# USB-C_Host_Shield.net
KiCad netlist of a schematic drawn in EAGLE
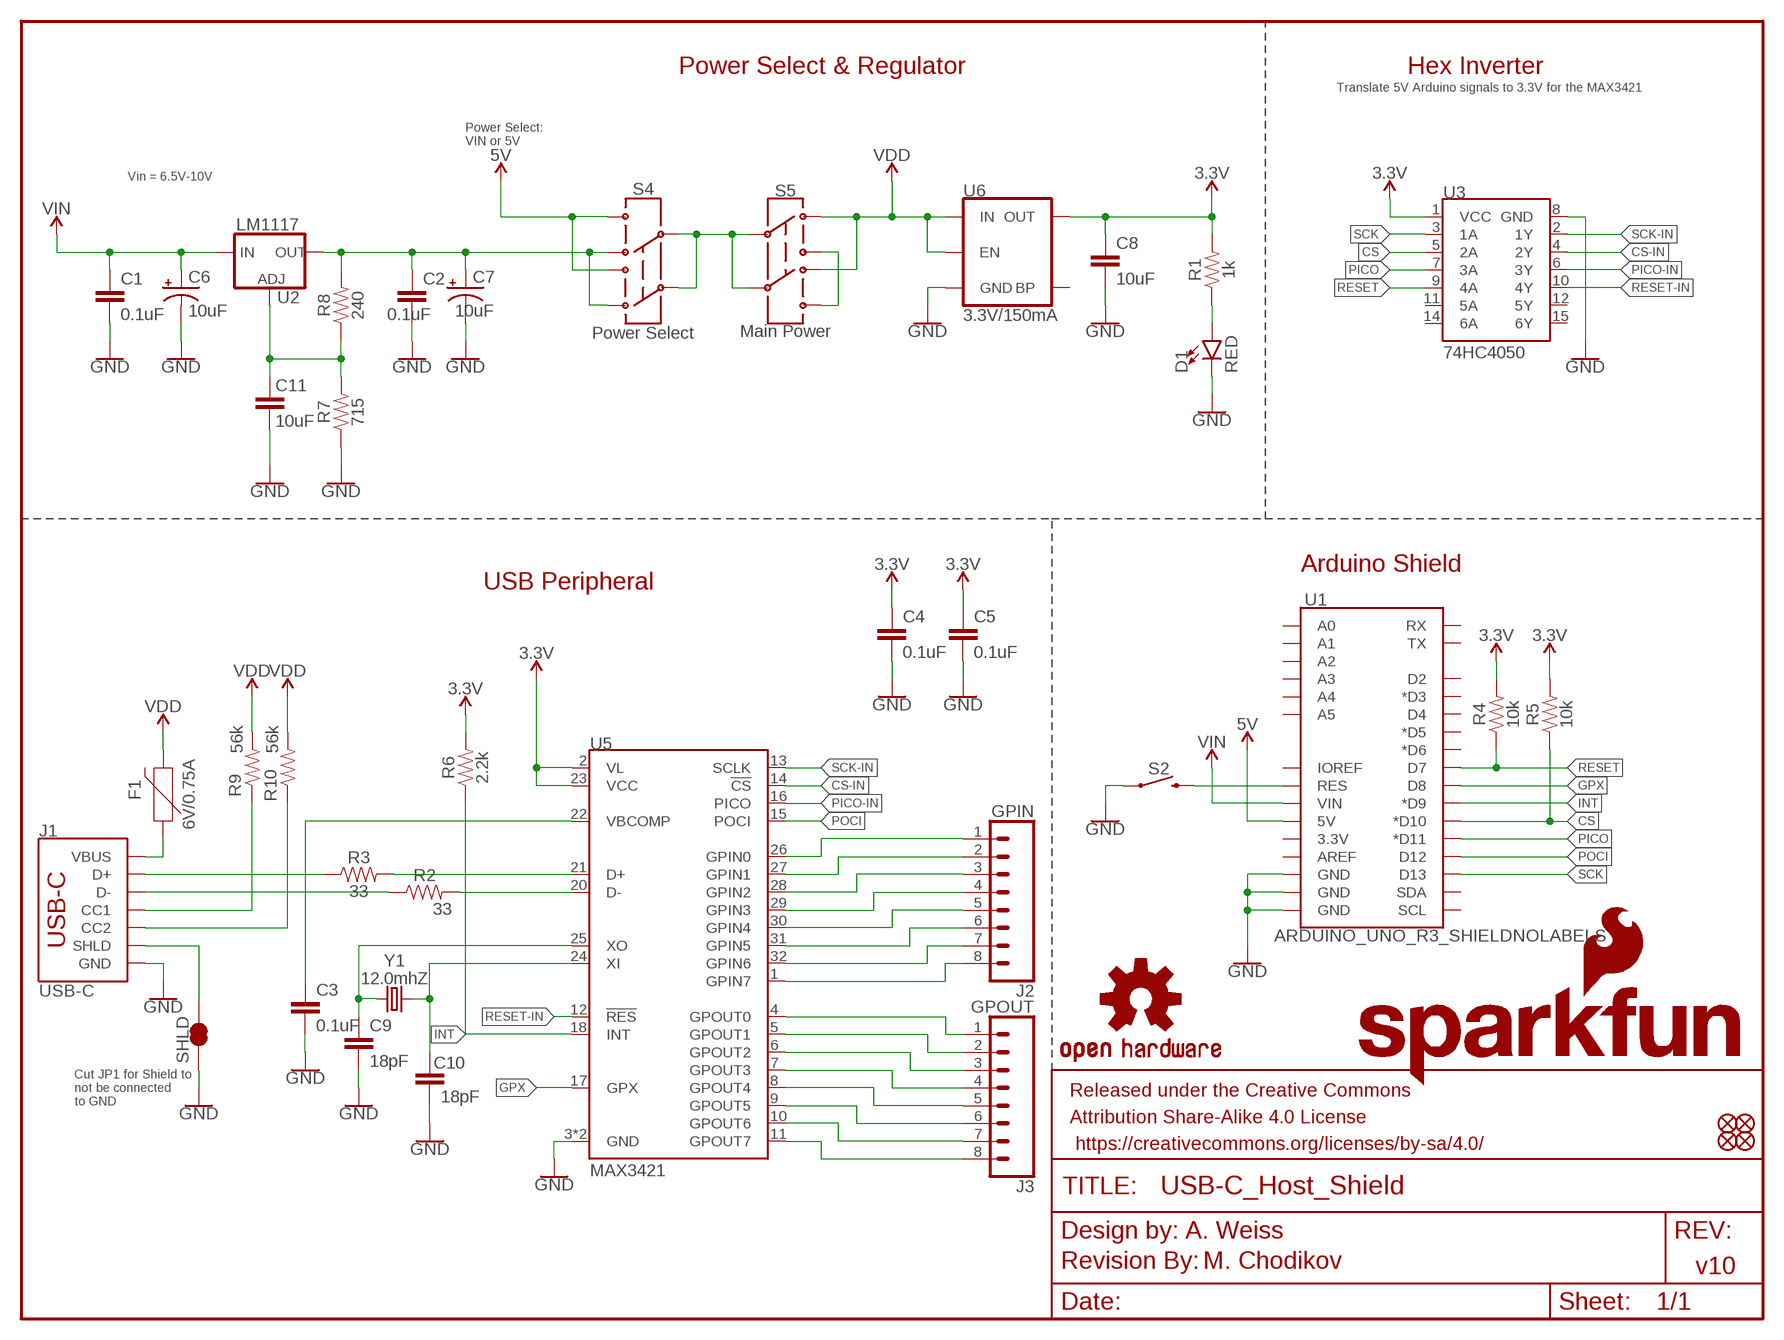
[diagram p0: schematic, sheet 1]

(export (version "E")
  (design (tool "Eeschema 10.0.6"))
  (components
    (comp (ref "C1")
      (value "0.1uF")
      (footprint "eagle-import:0603")
      (libsource (lib "eagle-import") (part "0.1UF-0603-25V-(+80/-20%)"))
    )
    (comp (ref "C2")
      (value "0.1uF")
      (footprint "eagle-import:0603")
      (libsource (lib "eagle-import") (part "0.1UF-0603-25V-(+80/-20%)"))
    )
    (comp (ref "C3")
      (value "0.1uF")
      (footprint "eagle-import:0603")
      (libsource (lib "eagle-import") (part "0.1UF-0603-25V-(+80/-20%)"))
    )
    (comp (ref "C4")
      (value "0.1uF")
      (footprint "eagle-import:0603")
      (libsource (lib "eagle-import") (part "0.1UF-0603-25V-(+80/-20%)"))
    )
    (comp (ref "C5")
      (value "0.1uF")
      (footprint "eagle-import:0603")
      (libsource (lib "eagle-import") (part "0.1UF-0603-25V-(+80/-20%)"))
    )
    (comp (ref "C6")
      (value "10uF")
      (footprint "eagle-import:EIA3216")
      (libsource (lib "eagle-import") (part "10UF-POLAR-EIA3216-16V-10%(TANT)"))
    )
    (comp (ref "C7")
      (value "10uF")
      (footprint "eagle-import:EIA3216")
      (libsource (lib "eagle-import") (part "10UF-POLAR-EIA3216-16V-10%(TANT)"))
    )
    (comp (ref "C8")
      (value "10uF")
      (footprint "eagle-import:0603")
      (libsource (lib "eagle-import") (part "10UF-0603-6.3V-20%"))
    )
    (comp (ref "C9")
      (value "18pF")
      (footprint "eagle-import:0603")
      (libsource (lib "eagle-import") (part "18PF-0603-50V-5%"))
    )
    (comp (ref "C10")
      (value "18pF")
      (footprint "eagle-import:0603")
      (libsource (lib "eagle-import") (part "18PF-0603-50V-5%"))
    )
    (comp (ref "C11")
      (value "10uF")
      (footprint "eagle-import:0805")
      (libsource (lib "eagle-import") (part "10UF-0805-25V-10%"))
    )
    (comp (ref "D1")
      (value "RED")
      (footprint "eagle-import:LED-0603")
      (libsource (lib "eagle-import") (part "LED-RED0603"))
    )
    (comp (ref "F1")
      (value "6V/0.75A")
      (footprint "eagle-import:1206")
      (libsource (lib "eagle-import") (part "PPTC_0.75A"))
    )
    (comp (ref "FD1")
      (value "FIDUCIALUFIDUCIAL")
      (footprint "eagle-import:FIDUCIAL-MICRO")
      (libsource (lib "eagle-import") (part "FIDUCIALUFIDUCIAL"))
    )
    (comp (ref "FD2")
      (value "FIDUCIALUFIDUCIAL")
      (footprint "eagle-import:FIDUCIAL-MICRO")
      (libsource (lib "eagle-import") (part "FIDUCIALUFIDUCIAL"))
    )
    (comp (ref "FD3")
      (value "FIDUCIALUFIDUCIAL")
      (footprint "eagle-import:FIDUCIAL-MICRO")
      (libsource (lib "eagle-import") (part "FIDUCIALUFIDUCIAL"))
    )
    (comp (ref "FD4")
      (value "FIDUCIALUFIDUCIAL")
      (footprint "eagle-import:FIDUCIAL-MICRO")
      (libsource (lib "eagle-import") (part "FIDUCIALUFIDUCIAL"))
    )
    (comp (ref "FRAME1")
      (value "FRAME-LETTER")
      (footprint "eagle-import:CREATIVE_COMMONS")
      (libsource (lib "eagle-import") (part "FRAME-LETTER"))
    )
    (comp (ref "J1")
      (value "USB-C")
      (footprint "eagle-import:USB-C-16P-2LAYER-PADS")
      (libsource (lib "eagle-import") (part "USB_C_2-LAYER_PADS"))
    )
    (comp (ref "J2")
      (value "GPIN")
      (footprint "eagle-import:1X08")
      (libsource (lib "eagle-import") (part "CONN_08{dblquote}"))
    )
    (comp (ref "J3")
      (value "GPOUT")
      (footprint "eagle-import:1X08")
      (libsource (lib "eagle-import") (part "CONN_08{dblquote}"))
    )
    (comp (ref "LOGO1")
      (value "OSHW-LOGOM")
      (footprint "eagle-import:OSHW-LOGO-M")
      (libsource (lib "eagle-import") (part "OSHW-LOGOM"))
    )
    (comp (ref "LOGO2")
      (value "SFE_LOGO_NAME_FLAME.1_INCH")
      (footprint "eagle-import:SFE_LOGO_NAME_FLAME_.1")
      (libsource (lib "eagle-import") (part "SFE_LOGO_NAME_FLAME.1_INCH"))
    )
    (comp (ref "LOGO3")
      (value "SFE_LOGO_NAME_FLAME.2_INCH")
      (footprint "eagle-import:SFE_LOGO_NAME_FLAME_.2")
      (libsource (lib "eagle-import") (part "SFE_LOGO_NAME_FLAME.2_INCH"))
    )
    (comp (ref "LOGO7")
      (value "REVISION")
      (footprint "eagle-import:REVISION")
      (libsource (lib "eagle-import") (part "REVISION"))
    )
    (comp (ref "R1")
      (value "1k")
      (footprint "eagle-import:0603")
      (libsource (lib "eagle-import") (part "1KOHM-0603-1/10W-1%"))
    )
    (comp (ref "R2")
      (value "33")
      (footprint "eagle-import:0603")
      (libsource (lib "eagle-import") (part "33OHM-0603-1/10W-1%"))
    )
    (comp (ref "R3")
      (value "33")
      (footprint "eagle-import:0603")
      (libsource (lib "eagle-import") (part "33OHM-0603-1/10W-1%"))
    )
    (comp (ref "R4")
      (value "10k")
      (footprint "eagle-import:0603")
      (libsource (lib "eagle-import") (part "10KOHM-0603-1/10W-1%"))
    )
    (comp (ref "R5")
      (value "10k")
      (footprint "eagle-import:0603")
      (libsource (lib "eagle-import") (part "10KOHM-0603-1/10W-1%"))
    )
    (comp (ref "R6")
      (value "2.2k")
      (footprint "eagle-import:0603")
      (libsource (lib "eagle-import") (part "2.2KOHM-0603-1/10W-1%"))
    )
    (comp (ref "R7")
      (value "715")
      (footprint "eagle-import:0603")
      (libsource (lib "eagle-import") (part "715OHM-0603-1/10W-1%"))
    )
    (comp (ref "R8")
      (value "240")
      (footprint "eagle-import:0603")
      (libsource (lib "eagle-import") (part "240OHM-0603-1/10W-1%"))
    )
    (comp (ref "R9")
      (value "56k")
      (footprint "eagle-import:0603")
      (libsource (lib "eagle-import") (part "56KOHM"))
    )
    (comp (ref "R10")
      (value "56k")
      (footprint "eagle-import:0603")
      (libsource (lib "eagle-import") (part "56KOHM"))
    )
    (comp (ref "S2")
      (value "MOMENTARY-SWITCH-SPST-SMD-5.2MM-TALL")
      (footprint "eagle-import:TACTILE_SWITCH_SMD_5.2MM")
      (libsource (lib "eagle-import") (part "MOMENTARY-SWITCH-SPST-SMD-5.2MM-TALL"))
    )
    (comp (ref "S4")
      (value "Power Select")
      (footprint "eagle-import:SWITCH_DPDT_SMD_AYZ0202")
      (libsource (lib "eagle-import") (part "SWITCH-DPDT-SMD-AYZ0202"))
    )
    (comp (ref "S5")
      (value "Main Power")
      (footprint "eagle-import:SWITCH_DPDT_SMD_AYZ0202")
      (libsource (lib "eagle-import") (part "SWITCH-DPDT-SMD-AYZ0202"))
    )
    (comp (ref "SHLD")
      (value "JUMPER-SMT_2_NC_TRACE_SILK")
      (footprint "eagle-import:SMT-JUMPER_2_NC_TRACE_SILK")
      (libsource (lib "eagle-import") (part "JUMPER-SMT_2_NC_TRACE_SILK"))
    )
    (comp (ref "U1")
      (value "ARDUINO_UNO_R3_SHIELDNOLABELS")
      (footprint "eagle-import:UNO_R3_SHIELD_NOLABELS")
      (libsource (lib "eagle-import") (part "ARDUINO_UNO_R3_SHIELDNOLABELS"))
    )
    (comp (ref "U2")
      (value "LM1117")
      (footprint "eagle-import:SOT223")
      (libsource (lib "eagle-import") (part "V_REG_LM1117SOT223"))
    )
    (comp (ref "U3")
      (value "74HC4050")
      (footprint "eagle-import:SO16")
      (libsource (lib "eagle-import") (part "HEX_CONVERTER"))
    )
    (comp (ref "U5")
      (value "MAX3421")
      (footprint "eagle-import:TQFP32")
      (libsource (lib "eagle-import") (part "MAX3421"))
    )
    (comp (ref "U6")
      (value "3.3V/150mA")
      (footprint "eagle-import:SOT23-5")
      (libsource (lib "eagle-import") (part "V_REG_MIC52053.3V"))
    )
    (comp (ref "Y1")
      (value "12.0mhZ")
      (footprint "eagle-import:CRYSTAL-SMD-2X2.5MM")
      (libsource (lib "eagle-import") (part "CRYSTAL-12MHZ"))
    )
  )
  (nets
    (net (code "1") (name "3.3V") (class "Default")
      (node (ref "C4") (pin "1") (pinfunction "1_1") (pintype "passive"))
      (node (ref "C5") (pin "1") (pinfunction "1_1") (pintype "passive"))
      (node (ref "C8") (pin "1") (pinfunction "1_1") (pintype "passive"))
      (node (ref "R1") (pin "2") (pinfunction "2_2") (pintype "passive"))
      (node (ref "R4") (pin "2") (pinfunction "2_2") (pintype "passive"))
      (node (ref "R5") (pin "2") (pinfunction "2_2") (pintype "passive"))
      (node (ref "R6") (pin "2") (pinfunction "2_2") (pintype "passive"))
      (node (ref "U3") (pin "1") (pinfunction "VCC_1") (pintype "bidirectional"))
      (node (ref "U5") (pin "2") (pinfunction "VL_2") (pintype "input"))
      (node (ref "U5") (pin "23") (pinfunction "VCC_23") (pintype "input"))
      (node (ref "U6") (pin "5") (pinfunction "OUT_5") (pintype "passive"))
    )
    (net (code "2") (name "5V") (class "Default")
      (node (ref "S4") (pin "1") (pinfunction "1_1") (pintype "bidirectional"))
      (node (ref "S4") (pin "4") (pinfunction "4_4") (pintype "bidirectional"))
      (node (ref "U1") (pin "5V") (pinfunction "5V_5V") (pintype "bidirectional"))
    )
    (net (code "3") (name "CS") (class "Default")
      (node (ref "R5") (pin "1") (pinfunction "1_1") (pintype "passive"))
      (node (ref "U1") (pin "D10") (pinfunction "*D10_D10") (pintype "bidirectional"))
      (node (ref "U3") (pin "5") (pinfunction "2A_5") (pintype "bidirectional"))
    )
    (net (code "4") (name "CS-IN") (class "Default")
      (node (ref "U3") (pin "4") (pinfunction "2Y_4") (pintype "bidirectional"))
      (node (ref "U5") (pin "14") (pinfunction "~{CS}_14") (pintype "input"))
    )
    (net (code "5") (name "GND") (class "Default")
      (node (ref "C1") (pin "2") (pinfunction "2_2") (pintype "passive"))
      (node (ref "C10") (pin "2") (pinfunction "2_2") (pintype "passive"))
      (node (ref "C11") (pin "2") (pinfunction "2_2") (pintype "passive"))
      (node (ref "C2") (pin "2") (pinfunction "2_2") (pintype "passive"))
      (node (ref "C3") (pin "2") (pinfunction "2_2") (pintype "passive"))
      (node (ref "C4") (pin "2") (pinfunction "2_2") (pintype "passive"))
      (node (ref "C5") (pin "2") (pinfunction "2_2") (pintype "passive"))
      (node (ref "C6") (pin "-") (pinfunction "-_-") (pintype "passive"))
      (node (ref "C7") (pin "-") (pinfunction "-_-") (pintype "passive"))
      (node (ref "C8") (pin "2") (pinfunction "2_2") (pintype "passive"))
      (node (ref "C9") (pin "2") (pinfunction "2_2") (pintype "passive"))
      (node (ref "D1") (pin "C") (pinfunction "C_C") (pintype "passive"))
      (node (ref "J1") (pin "GND") (pinfunction "GND_GND") (pintype "bidirectional"))
      (node (ref "J1") (pin "GND2") (pinfunction "GND_GND2") (pintype "bidirectional"))
      (node (ref "R7") (pin "1") (pinfunction "1_1") (pintype "passive"))
      (node (ref "S2") (pin "1") (pinfunction "1_1") (pintype "passive"))
      (node (ref "SHLD") (pin "1") (pinfunction "1_1") (pintype "passive"))
      (node (ref "U1") (pin "GND@0") (pinfunction "GND_GND@0") (pintype "bidirectional"))
      (node (ref "U1") (pin "GND@1") (pinfunction "GND_GND@1") (pintype "bidirectional"))
      (node (ref "U1") (pin "GND@2") (pinfunction "GND_GND@2") (pintype "bidirectional"))
      (node (ref "U3") (pin "8") (pinfunction "GND_8") (pintype "bidirectional"))
      (node (ref "U5") (pin "19") (pinfunction "GND_19") (pintype "input"))
      (node (ref "U5") (pin "3") (pinfunction "GND_3") (pintype "input"))
      (node (ref "U6") (pin "2") (pinfunction "GND_2") (pintype "input"))
    )
    (net (code "6") (name "GPX") (class "Default")
      (node (ref "U1") (pin "D8") (pinfunction "D8_D8") (pintype "bidirectional"))
      (node (ref "U5") (pin "17") (pinfunction "GPX_17") (pintype "output"))
    )
    (net (code "7") (name "INT") (class "Default")
      (node (ref "R6") (pin "1") (pinfunction "1_1") (pintype "passive"))
      (node (ref "U1") (pin "D9") (pinfunction "*D9_D9") (pintype "bidirectional"))
      (node (ref "U5") (pin "18") (pinfunction "INT_18") (pintype "output"))
    )
    (net (code "8") (name "Net-(C2-Pad1)") (class "Default")
      (node (ref "C2") (pin "1") (pinfunction "1_1") (pintype "passive"))
      (node (ref "C7") (pin "+") (pinfunction "+_+") (pintype "passive"))
      (node (ref "R8") (pin "2") (pinfunction "2_2") (pintype "passive"))
      (node (ref "S4") (pin "3") (pinfunction "3_3") (pintype "bidirectional"))
      (node (ref "S4") (pin "6") (pinfunction "6_6") (pintype "bidirectional"))
      (node (ref "U2") (pin "2") (pinfunction "OUT_2") (pintype "output"))
      (node (ref "U2") (pin "4") (pinfunction "OUT_4") (pintype "output"))
    )
    (net (code "9") (name "Net-(D1-PadA)") (class "Default")
      (node (ref "D1") (pin "A") (pinfunction "A_A") (pintype "passive"))
      (node (ref "R1") (pin "1") (pinfunction "1_1") (pintype "passive"))
    )
    (net (code "10") (name "Net-(F1-Pad1)") (class "Default")
      (node (ref "F1") (pin "1") (pinfunction "1_1") (pintype "bidirectional"))
      (node (ref "J1") (pin "VBUS1") (pinfunction "VBUS_VBUS1") (pintype "bidirectional"))
      (node (ref "J1") (pin "VBUS2") (pinfunction "VBUS_VBUS2") (pintype "bidirectional"))
    )
    (net (code "11") (name "Net-(J1-CC1)") (class "Default")
      (node (ref "J1") (pin "A5") (pinfunction "CC1_A5") (pintype "bidirectional"))
      (node (ref "R9") (pin "1") (pinfunction "1_1") (pintype "passive"))
    )
    (net (code "12") (name "Net-(J1-CC2)") (class "Default")
      (node (ref "J1") (pin "B5") (pinfunction "CC2_B5") (pintype "bidirectional"))
      (node (ref "R10") (pin "1") (pinfunction "1_1") (pintype "passive"))
    )
    (net (code "13") (name "Net-(J1-D+-PadA6)") (class "Default")
      (node (ref "J1") (pin "A6") (pinfunction "D+_A6") (pintype "bidirectional"))
      (node (ref "J1") (pin "B6") (pinfunction "D+_B6") (pintype "bidirectional"))
      (node (ref "R3") (pin "1") (pinfunction "1_1") (pintype "passive"))
    )
    (net (code "14") (name "Net-(J1-D--PadA7)") (class "Default")
      (node (ref "J1") (pin "A7") (pinfunction "D-_A7") (pintype "bidirectional"))
      (node (ref "J1") (pin "B7") (pinfunction "D-_B7") (pintype "bidirectional"))
      (node (ref "R2") (pin "1") (pinfunction "1_1") (pintype "passive"))
    )
    (net (code "15") (name "Net-(J1-SHLD-PadSHLD1)") (class "Default")
      (node (ref "J1") (pin "SHLD1") (pinfunction "SHLD_SHLD1") (pintype "bidirectional"))
      (node (ref "J1") (pin "SHLD2") (pinfunction "SHLD_SHLD2") (pintype "bidirectional"))
      (node (ref "J1") (pin "SHLD3") (pinfunction "SHLD_SHLD3") (pintype "bidirectional"))
      (node (ref "J1") (pin "SHLD4") (pinfunction "SHLD_SHLD4") (pintype "bidirectional"))
      (node (ref "SHLD") (pin "2") (pinfunction "2_2") (pintype "passive"))
    )
    (net (code "16") (name "Net-(S2-2)") (class "Default")
      (node (ref "S2") (pin "3") (pinfunction "2_3") (pintype "passive"))
      (node (ref "U1") (pin "RES") (pinfunction "RES_RES") (pintype "bidirectional"))
    )
    (net (code "17") (name "Net-(S4-Pad2)") (class "Default")
      (node (ref "S4") (pin "2") (pinfunction "2_2") (pintype "bidirectional"))
      (node (ref "S4") (pin "5") (pinfunction "5_5") (pintype "bidirectional"))
      (node (ref "S5") (pin "2") (pinfunction "2_2") (pintype "bidirectional"))
      (node (ref "S5") (pin "5") (pinfunction "5_5") (pintype "bidirectional"))
    )
    (net (code "18") (name "Net-(S5-Pad1)") (class "Default")
      (node (ref "S5") (pin "1") (pinfunction "1_1") (pintype "bidirectional"))
      (node (ref "S5") (pin "4") (pinfunction "4_4") (pintype "bidirectional"))
    )
    (net (code "19") (name "Net-(U2-ADJ)") (class "Default")
      (node (ref "C11") (pin "1") (pinfunction "1_1") (pintype "passive"))
      (node (ref "R7") (pin "2") (pinfunction "2_2") (pintype "passive"))
      (node (ref "R8") (pin "1") (pinfunction "1_1") (pintype "passive"))
      (node (ref "U2") (pin "1") (pinfunction "ADJ_1") (pintype "input"))
    )
    (net (code "20") (name "Net-(U5-D+)") (class "Default")
      (node (ref "R3") (pin "2") (pinfunction "2_2") (pintype "passive"))
      (node (ref "U5") (pin "21") (pinfunction "D+_21") (pintype "bidirectional"))
    )
    (net (code "21") (name "Net-(U5-D-)") (class "Default")
      (node (ref "R2") (pin "2") (pinfunction "2_2") (pintype "passive"))
      (node (ref "U5") (pin "20") (pinfunction "D-_20") (pintype "bidirectional"))
    )
    (net (code "22") (name "Net-(U5-GPIN0)") (class "Default")
      (node (ref "J2") (pin "1") (pinfunction "1_1") (pintype "passive"))
      (node (ref "U5") (pin "26") (pinfunction "GPIN0_26") (pintype "input"))
    )
    (net (code "23") (name "Net-(U5-GPIN1)") (class "Default")
      (node (ref "J2") (pin "2") (pinfunction "2_2") (pintype "passive"))
      (node (ref "U5") (pin "27") (pinfunction "GPIN1_27") (pintype "input"))
    )
    (net (code "24") (name "Net-(U5-GPIN2)") (class "Default")
      (node (ref "J2") (pin "3") (pinfunction "3_3") (pintype "passive"))
      (node (ref "U5") (pin "28") (pinfunction "GPIN2_28") (pintype "input"))
    )
    (net (code "25") (name "Net-(U5-GPIN3)") (class "Default")
      (node (ref "J2") (pin "4") (pinfunction "4_4") (pintype "passive"))
      (node (ref "U5") (pin "29") (pinfunction "GPIN3_29") (pintype "input"))
    )
    (net (code "26") (name "Net-(U5-GPIN4)") (class "Default")
      (node (ref "J2") (pin "5") (pinfunction "5_5") (pintype "passive"))
      (node (ref "U5") (pin "30") (pinfunction "GPIN4_30") (pintype "input"))
    )
    (net (code "27") (name "Net-(U5-GPIN5)") (class "Default")
      (node (ref "J2") (pin "6") (pinfunction "6_6") (pintype "passive"))
      (node (ref "U5") (pin "31") (pinfunction "GPIN5_31") (pintype "input"))
    )
    (net (code "28") (name "Net-(U5-GPIN6)") (class "Default")
      (node (ref "J2") (pin "7") (pinfunction "7_7") (pintype "passive"))
      (node (ref "U5") (pin "32") (pinfunction "GPIN6_32") (pintype "input"))
    )
    (net (code "29") (name "Net-(U5-GPIN7)") (class "Default")
      (node (ref "J2") (pin "8") (pinfunction "8_8") (pintype "passive"))
      (node (ref "U5") (pin "1") (pinfunction "GPIN7_1") (pintype "input"))
    )
    (net (code "30") (name "Net-(U5-GPOUT0)") (class "Default")
      (node (ref "J3") (pin "1") (pinfunction "1_1") (pintype "passive"))
      (node (ref "U5") (pin "4") (pinfunction "GPOUT0_4") (pintype "output"))
    )
    (net (code "31") (name "Net-(U5-GPOUT1)") (class "Default")
      (node (ref "J3") (pin "2") (pinfunction "2_2") (pintype "passive"))
      (node (ref "U5") (pin "5") (pinfunction "GPOUT1_5") (pintype "output"))
    )
    (net (code "32") (name "Net-(U5-GPOUT2)") (class "Default")
      (node (ref "J3") (pin "3") (pinfunction "3_3") (pintype "passive"))
      (node (ref "U5") (pin "6") (pinfunction "GPOUT2_6") (pintype "output"))
    )
    (net (code "33") (name "Net-(U5-GPOUT3)") (class "Default")
      (node (ref "J3") (pin "4") (pinfunction "4_4") (pintype "passive"))
      (node (ref "U5") (pin "7") (pinfunction "GPOUT3_7") (pintype "output"))
    )
    (net (code "34") (name "Net-(U5-GPOUT4)") (class "Default")
      (node (ref "J3") (pin "5") (pinfunction "5_5") (pintype "passive"))
      (node (ref "U5") (pin "8") (pinfunction "GPOUT4_8") (pintype "output"))
    )
    (net (code "35") (name "Net-(U5-GPOUT5)") (class "Default")
      (node (ref "J3") (pin "6") (pinfunction "6_6") (pintype "passive"))
      (node (ref "U5") (pin "9") (pinfunction "GPOUT5_9") (pintype "output"))
    )
    (net (code "36") (name "Net-(U5-GPOUT6)") (class "Default")
      (node (ref "J3") (pin "7") (pinfunction "7_7") (pintype "passive"))
      (node (ref "U5") (pin "10") (pinfunction "GPOUT6_10") (pintype "output"))
    )
    (net (code "37") (name "Net-(U5-GPOUT7)") (class "Default")
      (node (ref "J3") (pin "8") (pinfunction "8_8") (pintype "passive"))
      (node (ref "U5") (pin "11") (pinfunction "GPOUT7_11") (pintype "output"))
    )
    (net (code "38") (name "Net-(U5-VBCOMP)") (class "Default")
      (node (ref "C3") (pin "1") (pinfunction "1_1") (pintype "passive"))
      (node (ref "U5") (pin "22") (pinfunction "VBCOMP_22") (pintype "input"))
    )
    (net (code "39") (name "Net-(U5-XI)") (class "Default")
      (node (ref "C10") (pin "1") (pinfunction "1_1") (pintype "passive"))
      (node (ref "U5") (pin "24") (pinfunction "XI_24") (pintype "input"))
      (node (ref "Y1") (pin "P3") (pinfunction "2_P3") (pintype "passive"))
    )
    (net (code "40") (name "Net-(U5-XO)") (class "Default")
      (node (ref "C9") (pin "1") (pinfunction "1_1") (pintype "passive"))
      (node (ref "U5") (pin "25") (pinfunction "XO_25") (pintype "output"))
      (node (ref "Y1") (pin "P1") (pinfunction "1_P1") (pintype "passive"))
    )
    (net (code "41") (name "PICO") (class "Default")
      (node (ref "U1") (pin "D11") (pinfunction "*D11_D11") (pintype "bidirectional"))
      (node (ref "U3") (pin "7") (pinfunction "3A_7") (pintype "bidirectional"))
    )
    (net (code "42") (name "PICO-IN") (class "Default")
      (node (ref "U3") (pin "6") (pinfunction "3Y_6") (pintype "bidirectional"))
      (node (ref "U5") (pin "16") (pinfunction "PICO_16") (pintype "bidirectional"))
    )
    (net (code "43") (name "POCI") (class "Default")
      (node (ref "U1") (pin "D12") (pinfunction "D12_D12") (pintype "bidirectional"))
      (node (ref "U5") (pin "15") (pinfunction "POCI_15") (pintype "output"))
    )
    (net (code "44") (name "RESET") (class "Default")
      (node (ref "R4") (pin "1") (pinfunction "1_1") (pintype "passive"))
      (node (ref "U1") (pin "D7") (pinfunction "D7_D7") (pintype "bidirectional"))
      (node (ref "U3") (pin "9") (pinfunction "4A_9") (pintype "bidirectional"))
    )
    (net (code "45") (name "RESET-IN") (class "Default")
      (node (ref "U3") (pin "10") (pinfunction "4Y_10") (pintype "bidirectional"))
      (node (ref "U5") (pin "12") (pinfunction "~{RES}_12") (pintype "input"))
    )
    (net (code "46") (name "SCK") (class "Default")
      (node (ref "U1") (pin "D13") (pinfunction "D13_D13") (pintype "bidirectional"))
      (node (ref "U3") (pin "3") (pinfunction "1A_3") (pintype "bidirectional"))
    )
    (net (code "47") (name "SCK-IN") (class "Default")
      (node (ref "U3") (pin "2") (pinfunction "1Y_2") (pintype "bidirectional"))
      (node (ref "U5") (pin "13") (pinfunction "SCLK_13") (pintype "input"))
    )
    (net (code "48") (name "VDD") (class "Default")
      (node (ref "F1") (pin "2") (pinfunction "2_2") (pintype "bidirectional"))
      (node (ref "R10") (pin "2") (pinfunction "2_2") (pintype "passive"))
      (node (ref "R9") (pin "2") (pinfunction "2_2") (pintype "passive"))
      (node (ref "S5") (pin "3") (pinfunction "3_3") (pintype "bidirectional"))
      (node (ref "S5") (pin "6") (pinfunction "6_6") (pintype "bidirectional"))
      (node (ref "U6") (pin "1") (pinfunction "IN_1") (pintype "input"))
      (node (ref "U6") (pin "3") (pinfunction "EN_3") (pintype "input"))
    )
    (net (code "49") (name "VIN") (class "Default")
      (node (ref "C1") (pin "1") (pinfunction "1_1") (pintype "passive"))
      (node (ref "C6") (pin "+") (pinfunction "+_+") (pintype "passive"))
      (node (ref "U1") (pin "VIN") (pinfunction "VIN_VIN") (pintype "bidirectional"))
      (node (ref "U2") (pin "3") (pinfunction "IN_3") (pintype "input"))
    )
    (net (code "50") (name "unconnected-(U1-*D3-PadD3)") (class "Default")
      (node (ref "U1") (pin "D3") (pinfunction "*D3_D3") (pintype "bidirectional"))
    )
    (net (code "51") (name "unconnected-(U1-*D5-PadD5)") (class "Default")
      (node (ref "U1") (pin "D5") (pinfunction "*D5_D5") (pintype "bidirectional"))
    )
    (net (code "52") (name "unconnected-(U1-*D6-PadD6)") (class "Default")
      (node (ref "U1") (pin "D6") (pinfunction "*D6_D6") (pintype "bidirectional"))
    )
    (net (code "53") (name "unconnected-(U1-Pad3.3V)") (class "Default")
      (node (ref "U1") (pin "3.3V") (pinfunction "3.3V_3.3V") (pintype "bidirectional"))
    )
    (net (code "54") (name "unconnected-(U1-PadA0)") (class "Default")
      (node (ref "U1") (pin "A0") (pinfunction "A0_A0") (pintype "bidirectional"))
    )
    (net (code "55") (name "unconnected-(U1-PadA1)") (class "Default")
      (node (ref "U1") (pin "A1") (pinfunction "A1_A1") (pintype "bidirectional"))
    )
    (net (code "56") (name "unconnected-(U1-PadA2)") (class "Default")
      (node (ref "U1") (pin "A2") (pinfunction "A2_A2") (pintype "bidirectional"))
    )
    (net (code "57") (name "unconnected-(U1-PadA3)") (class "Default")
      (node (ref "U1") (pin "A3") (pinfunction "A3_A3") (pintype "bidirectional"))
    )
    (net (code "58") (name "unconnected-(U1-PadA4)") (class "Default")
      (node (ref "U1") (pin "A4") (pinfunction "A4_A4") (pintype "bidirectional"))
    )
    (net (code "59") (name "unconnected-(U1-PadA5)") (class "Default")
      (node (ref "U1") (pin "A5") (pinfunction "A5_A5") (pintype "bidirectional"))
    )
    (net (code "60") (name "unconnected-(U1-PadAREF)") (class "Default")
      (node (ref "U1") (pin "AREF") (pinfunction "AREF_AREF") (pintype "bidirectional"))
    )
    (net (code "61") (name "unconnected-(U1-PadD2)") (class "Default")
      (node (ref "U1") (pin "D2") (pinfunction "D2_D2") (pintype "bidirectional"))
    )
    (net (code "62") (name "unconnected-(U1-PadD4)") (class "Default")
      (node (ref "U1") (pin "D4") (pinfunction "D4_D4") (pintype "bidirectional"))
    )
    (net (code "63") (name "unconnected-(U1-PadIOREF)") (class "Default")
      (node (ref "U1") (pin "IOREF") (pinfunction "IOREF_IOREF") (pintype "bidirectional"))
    )
    (net (code "64") (name "unconnected-(U1-PadRX)") (class "Default")
      (node (ref "U1") (pin "RX") (pinfunction "RX_RX") (pintype "bidirectional"))
    )
    (net (code "65") (name "unconnected-(U1-PadSCL)") (class "Default")
      (node (ref "U1") (pin "SCL") (pinfunction "SCL_SCL") (pintype "bidirectional"))
    )
    (net (code "66") (name "unconnected-(U1-PadSDA)") (class "Default")
      (node (ref "U1") (pin "SDA") (pinfunction "SDA_SDA") (pintype "bidirectional"))
    )
    (net (code "67") (name "unconnected-(U1-PadTX)") (class "Default")
      (node (ref "U1") (pin "TX") (pinfunction "TX_TX") (pintype "bidirectional"))
    )
    (net (code "68") (name "unconnected-(U3-5A-Pad11)") (class "Default")
      (node (ref "U3") (pin "11") (pinfunction "5A_11") (pintype "bidirectional"))
    )
    (net (code "69") (name "unconnected-(U3-5Y-Pad12)") (class "Default")
      (node (ref "U3") (pin "12") (pinfunction "5Y_12") (pintype "bidirectional"))
    )
    (net (code "70") (name "unconnected-(U3-6A-Pad14)") (class "Default")
      (node (ref "U3") (pin "14") (pinfunction "6A_14") (pintype "bidirectional"))
    )
    (net (code "71") (name "unconnected-(U3-6Y-Pad15)") (class "Default")
      (node (ref "U3") (pin "15") (pinfunction "6Y_15") (pintype "bidirectional"))
    )
    (net (code "72") (name "unconnected-(U6-BP-Pad4)") (class "Default")
      (node (ref "U6") (pin "4") (pinfunction "BP_4") (pintype "input"))
    )
  )
)
